# scr_precharge.net
KiCad netlist of a schematic drawn in EAGLE
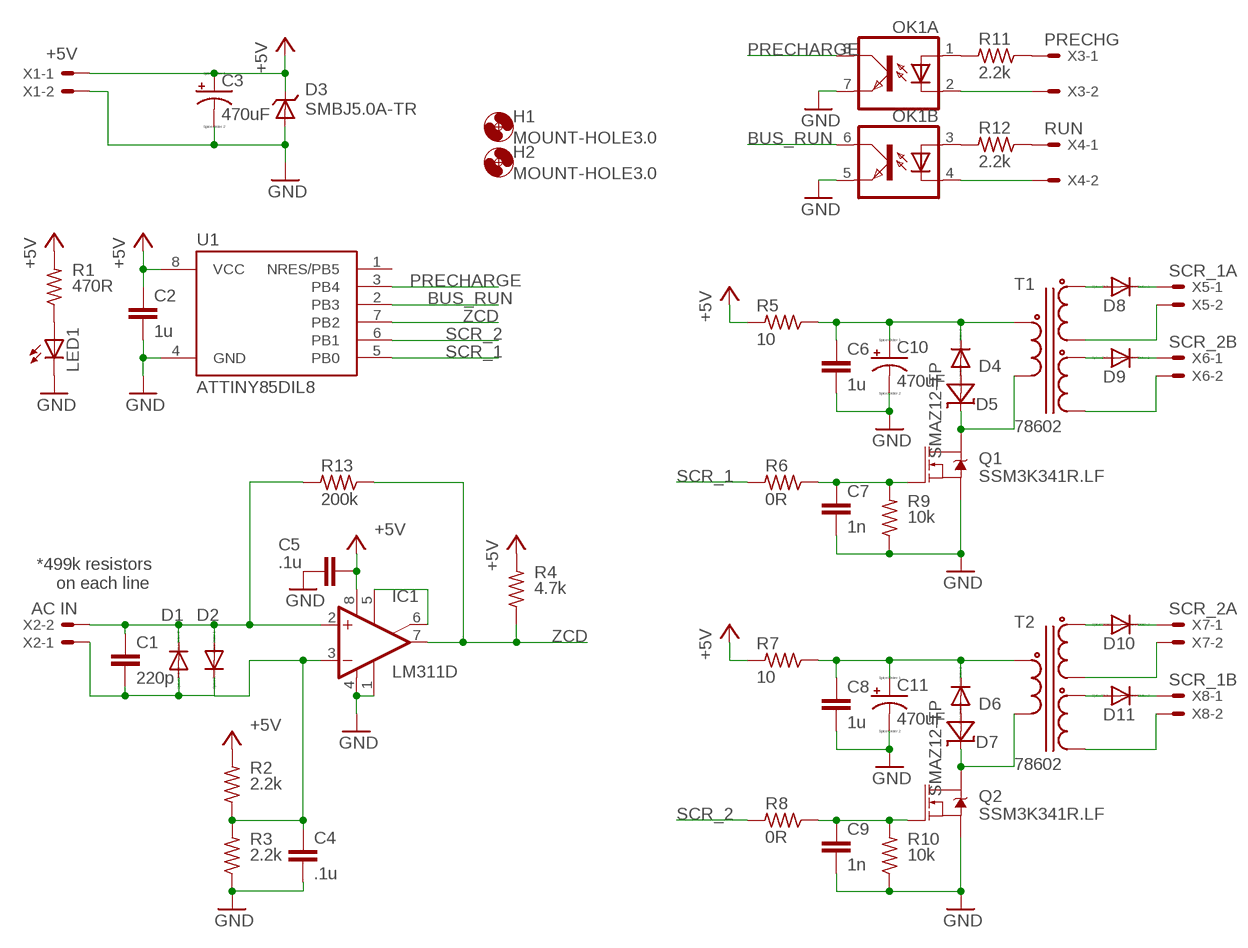
[diagram p0: schematic, sheet 1]

(export (version "E")
  (design (tool "Eeschema 10.0.6"))
  (components
    (comp (ref "C1")
      (value "220p")
      (footprint "eagle-import:C0805")
      (libsource (lib "eagle-import") (part "C-EUC0805"))
    )
    (comp (ref "C2")
      (value "1u")
      (footprint "eagle-import:C0805")
      (libsource (lib "eagle-import") (part "C-EUC0805"))
    )
    (comp (ref "C3")
      (value "470uF")
      (footprint "eagle-import:E3,5-8")
      (libsource (lib "eagle-import") (part "CPOL-USE3.5-8"))
    )
    (comp (ref "C4")
      (value ".1u")
      (footprint "eagle-import:C0805")
      (libsource (lib "eagle-import") (part "C-EUC0805"))
    )
    (comp (ref "C5")
      (value ".1u")
      (footprint "eagle-import:C0805")
      (libsource (lib "eagle-import") (part "C-EUC0805"))
    )
    (comp (ref "C6")
      (value "1u")
      (footprint "eagle-import:C0805")
      (libsource (lib "eagle-import") (part "C-EUC0805"))
    )
    (comp (ref "C7")
      (value "1n")
      (footprint "eagle-import:C0805")
      (libsource (lib "eagle-import") (part "C-EUC0805"))
    )
    (comp (ref "C8")
      (value "1u")
      (footprint "eagle-import:C0805")
      (libsource (lib "eagle-import") (part "C-EUC0805"))
    )
    (comp (ref "C9")
      (value "1n")
      (footprint "eagle-import:C0805")
      (libsource (lib "eagle-import") (part "C-EUC0805"))
    )
    (comp (ref "C10")
      (value "470uF")
      (footprint "eagle-import:E3,5-8")
      (libsource (lib "eagle-import") (part "CPOL-USE3.5-8"))
    )
    (comp (ref "C11")
      (value "470uF")
      (footprint "eagle-import:E3,5-8")
      (libsource (lib "eagle-import") (part "CPOL-USE3.5-8"))
    )
    (comp (ref "D1")
      (value "1N4148MICROMELF")
      (footprint "eagle-import:MICROMELF-W")
      (libsource (lib "eagle-import") (part "1N4148MICROMELF"))
    )
    (comp (ref "D2")
      (value "1N4148MICROMELF")
      (footprint "eagle-import:MICROMELF-W")
      (libsource (lib "eagle-import") (part "1N4148MICROMELF"))
    )
    (comp (ref "D3")
      (value "SMBJ5.0A-TR")
      (footprint "eagle-import:DO214AA")
      (libsource (lib "eagle-import") (part "SMBJ5.0A-TR"))
    )
    (comp (ref "D4")
      (value "1N4148MICROMELF")
      (footprint "eagle-import:MICROMELF-W")
      (libsource (lib "eagle-import") (part "1N4148MICROMELF"))
    )
    (comp (ref "D5")
      (value "SMAZ12-TP")
      (footprint "eagle-import:DO-214AC")
      (libsource (lib "eagle-import") (part "SMAZ12-TP"))
    )
    (comp (ref "D6")
      (value "1N4148MICROMELF")
      (footprint "eagle-import:MICROMELF-W")
      (libsource (lib "eagle-import") (part "1N4148MICROMELF"))
    )
    (comp (ref "D7")
      (value "SMAZ12-TP")
      (footprint "eagle-import:DO-214AC")
      (libsource (lib "eagle-import") (part "SMAZ12-TP"))
    )
    (comp (ref "D8")
      (value "1N4148MICROMELF")
      (footprint "eagle-import:MICROMELF-W")
      (libsource (lib "eagle-import") (part "1N4148MICROMELF"))
    )
    (comp (ref "D9")
      (value "1N4148MICROMELF")
      (footprint "eagle-import:MICROMELF-W")
      (libsource (lib "eagle-import") (part "1N4148MICROMELF"))
    )
    (comp (ref "D10")
      (value "1N4148MICROMELF")
      (footprint "eagle-import:MICROMELF-W")
      (libsource (lib "eagle-import") (part "1N4148MICROMELF"))
    )
    (comp (ref "D11")
      (value "1N4148MICROMELF")
      (footprint "eagle-import:MICROMELF-W")
      (libsource (lib "eagle-import") (part "1N4148MICROMELF"))
    )
    (comp (ref "H1")
      (value "MOUNT-HOLE3.0")
      (footprint "eagle-import:3,0")
      (libsource (lib "eagle-import") (part "MOUNT-HOLE3.0"))
    )
    (comp (ref "H2")
      (value "MOUNT-HOLE3.0")
      (footprint "eagle-import:3,0")
      (libsource (lib "eagle-import") (part "MOUNT-HOLE3.0"))
    )
    (comp (ref "IC1")
      (value "LM311D")
      (footprint "eagle-import:SO08")
      (libsource (lib "eagle-import") (part "LM311D"))
    )
    (comp (ref "LED1")
      (value "LEDCHIP-LED0805")
      (footprint "eagle-import:CHIP-LED0805")
      (libsource (lib "eagle-import") (part "LEDCHIP-LED0805"))
    )
    (comp (ref "OK1")
      (value "ILD621")
      (footprint "eagle-import:DIL08")
      (fields (field (name "MF") "VISHAY/TELEFUNKEN"))
      (libsource (lib "eagle-import") (part "ILD621"))
    )
    (comp (ref "Q1")
      (value "SSM3K341R.LF")
      (footprint "eagle-import:SOT23-3")
      (libsource (lib "eagle-import") (part "MOSFET-NCH-AO3404A"))
    )
    (comp (ref "Q2")
      (value "SSM3K341R.LF")
      (footprint "eagle-import:SOT23-3")
      (libsource (lib "eagle-import") (part "MOSFET-NCH-AO3404A"))
    )
    (comp (ref "R1")
      (value "470R")
      (footprint "eagle-import:R0805")
      (libsource (lib "eagle-import") (part "R-US_R0805"))
    )
    (comp (ref "R2")
      (value "2.2k")
      (footprint "eagle-import:R0805")
      (libsource (lib "eagle-import") (part "R-US_R0805"))
    )
    (comp (ref "R3")
      (value "2.2k")
      (footprint "eagle-import:R0805")
      (libsource (lib "eagle-import") (part "R-US_R0805"))
    )
    (comp (ref "R4")
      (value "4.7k")
      (footprint "eagle-import:R0805")
      (libsource (lib "eagle-import") (part "R-US_R0805"))
    )
    (comp (ref "R5")
      (value "10")
      (footprint "eagle-import:R2010")
      (libsource (lib "eagle-import") (part "R-US_R2010"))
    )
    (comp (ref "R6")
      (value "0R")
      (footprint "eagle-import:R0805")
      (libsource (lib "eagle-import") (part "R-US_R0805"))
    )
    (comp (ref "R7")
      (value "10")
      (footprint "eagle-import:R2010")
      (libsource (lib "eagle-import") (part "R-US_R2010"))
    )
    (comp (ref "R8")
      (value "0R")
      (footprint "eagle-import:R0805")
      (libsource (lib "eagle-import") (part "R-US_R0805"))
    )
    (comp (ref "R9")
      (value "10k")
      (footprint "eagle-import:R0805")
      (libsource (lib "eagle-import") (part "R-US_R0805"))
    )
    (comp (ref "R10")
      (value "10k")
      (footprint "eagle-import:R0805")
      (libsource (lib "eagle-import") (part "R-US_R0805"))
    )
    (comp (ref "R11")
      (value "2.2k")
      (footprint "eagle-import:R0805")
      (libsource (lib "eagle-import") (part "R-US_R0805"))
    )
    (comp (ref "R12")
      (value "2.2k")
      (footprint "eagle-import:R0805")
      (libsource (lib "eagle-import") (part "R-US_R0805"))
    )
    (comp (ref "R13")
      (value "200k")
      (footprint "eagle-import:R0805")
      (libsource (lib "eagle-import") (part "R-US_R0805"))
    )
    (comp (ref "T1")
      (value "78602")
      (footprint "eagle-import:J-STD-020D")
      (libsource (lib "eagle-import") (part "78602"))
    )
    (comp (ref "T2")
      (value "78602")
      (footprint "eagle-import:J-STD-020D")
      (libsource (lib "eagle-import") (part "78602"))
    )
    (comp (ref "U1")
      (value "ATTINY85DIL8")
      (footprint "eagle-import:DIL8")
      (libsource (lib "eagle-import") (part "ATTINY85DIL8"))
    )
    (comp (ref "X1")
      (value "+5V")
      (footprint "eagle-import:22-23-2021")
      (fields (field (name "MF") "MOLEX") (field (name "MPN") "22-23-2021"))
      (libsource (lib "eagle-import") (part "22-23-2021"))
    )
    (comp (ref "X2")
      (value "AC IN")
      (footprint "eagle-import:22-23-2021")
      (fields (field (name "MF") "MOLEX") (field (name "MPN") "22-23-2021"))
      (libsource (lib "eagle-import") (part "22-23-2021"))
    )
    (comp (ref "X3")
      (value "PRECHG")
      (footprint "eagle-import:22-23-2021")
      (fields (field (name "MF") "MOLEX") (field (name "MPN") "22-23-2021"))
      (libsource (lib "eagle-import") (part "22-23-2021"))
    )
    (comp (ref "X4")
      (value "RUN")
      (footprint "eagle-import:22-23-2021")
      (fields (field (name "MF") "MOLEX") (field (name "MPN") "22-23-2021"))
      (libsource (lib "eagle-import") (part "22-23-2021"))
    )
    (comp (ref "X5")
      (value "SCR_1A")
      (footprint "eagle-import:22-23-2021")
      (fields (field (name "MF") "MOLEX") (field (name "MPN") "22-23-2021"))
      (libsource (lib "eagle-import") (part "22-23-2021"))
    )
    (comp (ref "X6")
      (value "SCR_2B")
      (footprint "eagle-import:22-23-2021")
      (fields (field (name "MF") "MOLEX") (field (name "MPN") "22-23-2021"))
      (libsource (lib "eagle-import") (part "22-23-2021"))
    )
    (comp (ref "X7")
      (value "SCR_2A")
      (footprint "eagle-import:22-23-2021")
      (fields (field (name "MF") "MOLEX") (field (name "MPN") "22-23-2021"))
      (libsource (lib "eagle-import") (part "22-23-2021"))
    )
    (comp (ref "X8")
      (value "SCR_1B")
      (footprint "eagle-import:22-23-2021")
      (fields (field (name "MF") "MOLEX") (field (name "MPN") "22-23-2021"))
      (libsource (lib "eagle-import") (part "22-23-2021"))
    )
  )
  (nets
    (net (code "1") (name "+5V") (class "Default")
      (node (ref "C2") (pin "1") (pinfunction "1_1") (pintype "passive"))
      (node (ref "C3") (pin "+") (pinfunction "+_+") (pintype "passive"))
      (node (ref "C5") (pin "2") (pinfunction "2_2") (pintype "passive"))
      (node (ref "D3") (pin "C") (pinfunction "C_C") (pintype "passive"))
      (node (ref "IC1") (pin "8") (pinfunction "V+_8") (pintype "power_in"))
      (node (ref "R1") (pin "2") (pinfunction "2_2") (pintype "passive"))
      (node (ref "R2") (pin "2") (pinfunction "2_2") (pintype "passive"))
      (node (ref "R4") (pin "2") (pinfunction "2_2") (pintype "passive"))
      (node (ref "R5") (pin "2") (pinfunction "2_2") (pintype "passive"))
      (node (ref "R7") (pin "2") (pinfunction "2_2") (pintype "passive"))
      (node (ref "U1") (pin "8") (pinfunction "VCC_8") (pintype "power_in"))
      (node (ref "X1") (pin "1") (pinfunction "S_1") (pintype "passive"))
    )
    (net (code "2") (name "/BUS_RUN") (class "Default")
      (node (ref "OK1") (pin "6") (pinfunction "COL_6") (pintype "passive"))
      (node (ref "U1") (pin "2") (pinfunction "PB3_2") (pintype "bidirectional"))
    )
    (net (code "3") (name "/PRECHARGE") (class "Default")
      (node (ref "OK1") (pin "8") (pinfunction "COL_8") (pintype "passive"))
      (node (ref "U1") (pin "3") (pinfunction "PB4_3") (pintype "bidirectional"))
    )
    (net (code "4") (name "/SCR_1") (class "Default")
      (node (ref "R6") (pin "2") (pinfunction "2_2") (pintype "passive"))
      (node (ref "U1") (pin "5") (pinfunction "PB0_5") (pintype "bidirectional"))
    )
    (net (code "5") (name "/SCR_2") (class "Default")
      (node (ref "R8") (pin "2") (pinfunction "2_2") (pintype "passive"))
      (node (ref "U1") (pin "6") (pinfunction "PB1_6") (pintype "bidirectional"))
    )
    (net (code "6") (name "/ZCD") (class "Default")
      (node (ref "IC1") (pin "7") (pinfunction "OUT_7") (pintype "output"))
      (node (ref "R13") (pin "1") (pinfunction "1_1") (pintype "passive"))
      (node (ref "R4") (pin "1") (pinfunction "1_1") (pintype "passive"))
      (node (ref "U1") (pin "7") (pinfunction "PB2_7") (pintype "bidirectional"))
    )
    (net (code "7") (name "GND") (class "Default")
      (node (ref "C10") (pin "-") (pinfunction "-_-") (pintype "passive"))
      (node (ref "C11") (pin "-") (pinfunction "-_-") (pintype "passive"))
      (node (ref "C2") (pin "2") (pinfunction "2_2") (pintype "passive"))
      (node (ref "C3") (pin "-") (pinfunction "-_-") (pintype "passive"))
      (node (ref "C4") (pin "2") (pinfunction "2_2") (pintype "passive"))
      (node (ref "C5") (pin "1") (pinfunction "1_1") (pintype "passive"))
      (node (ref "C6") (pin "2") (pinfunction "2_2") (pintype "passive"))
      (node (ref "C7") (pin "2") (pinfunction "2_2") (pintype "passive"))
      (node (ref "C8") (pin "2") (pinfunction "2_2") (pintype "passive"))
      (node (ref "C9") (pin "2") (pinfunction "2_2") (pintype "passive"))
      (node (ref "D3") (pin "A") (pinfunction "A_A") (pintype "passive"))
      (node (ref "IC1") (pin "1") (pinfunction "GND_1") (pintype "passive"))
      (node (ref "IC1") (pin "4") (pinfunction "V-_4") (pintype "power_in"))
      (node (ref "LED1") (pin "C") (pinfunction "C_C") (pintype "passive"))
      (node (ref "OK1") (pin "5") (pinfunction "EMIT_5") (pintype "passive"))
      (node (ref "OK1") (pin "7") (pinfunction "EMIT_7") (pintype "passive"))
      (node (ref "Q1") (pin "2") (pinfunction "S_2") (pintype "bidirectional"))
      (node (ref "Q2") (pin "2") (pinfunction "S_2") (pintype "bidirectional"))
      (node (ref "R10") (pin "1") (pinfunction "1_1") (pintype "passive"))
      (node (ref "R3") (pin "1") (pinfunction "1_1") (pintype "passive"))
      (node (ref "R9") (pin "1") (pinfunction "1_1") (pintype "passive"))
      (node (ref "U1") (pin "4") (pinfunction "GND_4") (pintype "power_in"))
      (node (ref "X1") (pin "2") (pinfunction "S_2") (pintype "passive"))
    )
    (net (code "8") (name "Net-(C10-Pad+)") (class "Default")
      (node (ref "C10") (pin "+") (pinfunction "+_+") (pintype "passive"))
      (node (ref "C6") (pin "1") (pinfunction "1_1") (pintype "passive"))
      (node (ref "D4") (pin "C") (pinfunction "C_C") (pintype "passive"))
      (node (ref "R5") (pin "1") (pinfunction "1_1") (pintype "passive"))
      (node (ref "T1") (pin "P$1") (pinfunction "P$1_P$1") (pintype "bidirectional"))
    )
    (net (code "9") (name "Net-(C11-Pad+)") (class "Default")
      (node (ref "C11") (pin "+") (pinfunction "+_+") (pintype "passive"))
      (node (ref "C8") (pin "1") (pinfunction "1_1") (pintype "passive"))
      (node (ref "D6") (pin "C") (pinfunction "C_C") (pintype "passive"))
      (node (ref "R7") (pin "1") (pinfunction "1_1") (pintype "passive"))
      (node (ref "T2") (pin "P$1") (pinfunction "P$1_P$1") (pintype "bidirectional"))
    )
    (net (code "10") (name "Net-(D4-PadA)") (class "Default")
      (node (ref "D4") (pin "A") (pinfunction "A_A") (pintype "passive"))
      (node (ref "D5") (pin "A") (pinfunction "A_A") (pintype "passive"))
    )
    (net (code "11") (name "Net-(D6-PadA)") (class "Default")
      (node (ref "D6") (pin "A") (pinfunction "A_A") (pintype "passive"))
      (node (ref "D7") (pin "A") (pinfunction "A_A") (pintype "passive"))
    )
    (net (code "12") (name "Net-(D8-PadA)") (class "Default")
      (node (ref "D8") (pin "A") (pinfunction "A_A") (pintype "passive"))
      (node (ref "T1") (pin "P$2") (pinfunction "P$2_P$2") (pintype "bidirectional"))
    )
    (net (code "13") (name "Net-(D9-PadA)") (class "Default")
      (node (ref "D9") (pin "A") (pinfunction "A_A") (pintype "passive"))
      (node (ref "T1") (pin "P$3") (pinfunction "P$3_P$3") (pintype "bidirectional"))
    )
    (net (code "14") (name "Net-(D10-PadA)") (class "Default")
      (node (ref "D10") (pin "A") (pinfunction "A_A") (pintype "passive"))
      (node (ref "T2") (pin "P$2") (pinfunction "P$2_P$2") (pintype "bidirectional"))
    )
    (net (code "15") (name "Net-(D11-PadA)") (class "Default")
      (node (ref "D11") (pin "A") (pinfunction "A_A") (pintype "passive"))
      (node (ref "T2") (pin "P$3") (pinfunction "P$3_P$3") (pintype "bidirectional"))
    )
    (net (code "16") (name "Net-(IC1-+IN)") (class "Default")
      (node (ref "C1") (pin "1") (pinfunction "1_1") (pintype "passive"))
      (node (ref "D1") (pin "C") (pinfunction "C_C") (pintype "passive"))
      (node (ref "D2") (pin "A") (pinfunction "A_A") (pintype "passive"))
      (node (ref "IC1") (pin "2") (pinfunction "+IN_2") (pintype "input"))
      (node (ref "R13") (pin "2") (pinfunction "2_2") (pintype "passive"))
      (node (ref "X2") (pin "2") (pinfunction "S_2") (pintype "passive"))
    )
    (net (code "17") (name "Net-(IC1--IN)") (class "Default")
      (node (ref "C1") (pin "2") (pinfunction "2_2") (pintype "passive"))
      (node (ref "C4") (pin "1") (pinfunction "1_1") (pintype "passive"))
      (node (ref "D1") (pin "A") (pinfunction "A_A") (pintype "passive"))
      (node (ref "D2") (pin "C") (pinfunction "C_C") (pintype "passive"))
      (node (ref "IC1") (pin "3") (pinfunction "-IN_3") (pintype "input"))
      (node (ref "R2") (pin "1") (pinfunction "1_1") (pintype "passive"))
      (node (ref "R3") (pin "2") (pinfunction "2_2") (pintype "passive"))
      (node (ref "X2") (pin "1") (pinfunction "S_1") (pintype "passive"))
    )
    (net (code "18") (name "Net-(IC1-ON)") (class "Default")
      (node (ref "IC1") (pin "5") (pinfunction "ON_5") (pintype "passive"))
      (node (ref "IC1") (pin "6") (pinfunction "ON/STR_6") (pintype "passive"))
    )
    (net (code "19") (name "Net-(LED1-PadA)") (class "Default")
      (node (ref "LED1") (pin "A") (pinfunction "A_A") (pintype "passive"))
      (node (ref "R1") (pin "1") (pinfunction "1_1") (pintype "passive"))
    )
    (net (code "20") (name "Net-(OK1A-A)") (class "Default")
      (node (ref "OK1") (pin "1") (pinfunction "A_1") (pintype "passive"))
      (node (ref "R11") (pin "2") (pinfunction "2_2") (pintype "passive"))
    )
    (net (code "21") (name "Net-(OK1A-C)") (class "Default")
      (node (ref "OK1") (pin "2") (pinfunction "C_2") (pintype "passive"))
      (node (ref "X3") (pin "2") (pinfunction "S_2") (pintype "passive"))
    )
    (net (code "22") (name "Net-(OK1B-A)") (class "Default")
      (node (ref "OK1") (pin "3") (pinfunction "A_3") (pintype "passive"))
      (node (ref "R12") (pin "2") (pinfunction "2_2") (pintype "passive"))
    )
    (net (code "23") (name "Net-(OK1B-C)") (class "Default")
      (node (ref "OK1") (pin "4") (pinfunction "C_4") (pintype "passive"))
      (node (ref "X4") (pin "2") (pinfunction "S_2") (pintype "passive"))
    )
    (net (code "24") (name "Net-(Q1-D)") (class "Default")
      (node (ref "D5") (pin "C") (pinfunction "C_C") (pintype "passive"))
      (node (ref "Q1") (pin "3") (pinfunction "D_3") (pintype "bidirectional"))
      (node (ref "T1") (pin "P$6") (pinfunction "P$6_P$6") (pintype "bidirectional"))
    )
    (net (code "25") (name "Net-(Q1-G)") (class "Default")
      (node (ref "C7") (pin "1") (pinfunction "1_1") (pintype "passive"))
      (node (ref "Q1") (pin "1") (pinfunction "G_1") (pintype "bidirectional"))
      (node (ref "R6") (pin "1") (pinfunction "1_1") (pintype "passive"))
      (node (ref "R9") (pin "2") (pinfunction "2_2") (pintype "passive"))
    )
    (net (code "26") (name "Net-(Q2-D)") (class "Default")
      (node (ref "D7") (pin "C") (pinfunction "C_C") (pintype "passive"))
      (node (ref "Q2") (pin "3") (pinfunction "D_3") (pintype "bidirectional"))
      (node (ref "T2") (pin "P$6") (pinfunction "P$6_P$6") (pintype "bidirectional"))
    )
    (net (code "27") (name "Net-(Q2-G)") (class "Default")
      (node (ref "C9") (pin "1") (pinfunction "1_1") (pintype "passive"))
      (node (ref "Q2") (pin "1") (pinfunction "G_1") (pintype "bidirectional"))
      (node (ref "R10") (pin "2") (pinfunction "2_2") (pintype "passive"))
      (node (ref "R8") (pin "1") (pinfunction "1_1") (pintype "passive"))
    )
    (net (code "28") (name "Net-(X3A-S)") (class "Default")
      (node (ref "R11") (pin "1") (pinfunction "1_1") (pintype "passive"))
      (node (ref "X3") (pin "1") (pinfunction "S_1") (pintype "passive"))
    )
    (net (code "29") (name "Net-(X4A-S)") (class "Default")
      (node (ref "R12") (pin "1") (pinfunction "1_1") (pintype "passive"))
      (node (ref "X4") (pin "1") (pinfunction "S_1") (pintype "passive"))
    )
    (net (code "30") (name "Net-(X5A-S)") (class "Default")
      (node (ref "D8") (pin "C") (pinfunction "C_C") (pintype "passive"))
      (node (ref "X5") (pin "1") (pinfunction "S_1") (pintype "passive"))
    )
    (net (code "31") (name "Net-(X5B-S)") (class "Default")
      (node (ref "T1") (pin "P$5") (pinfunction "P$5_P$5") (pintype "bidirectional"))
      (node (ref "X5") (pin "2") (pinfunction "S_2") (pintype "passive"))
    )
    (net (code "32") (name "Net-(X6A-S)") (class "Default")
      (node (ref "D9") (pin "C") (pinfunction "C_C") (pintype "passive"))
      (node (ref "X6") (pin "1") (pinfunction "S_1") (pintype "passive"))
    )
    (net (code "33") (name "Net-(X6B-S)") (class "Default")
      (node (ref "T1") (pin "P$4") (pinfunction "P$4_P$4") (pintype "bidirectional"))
      (node (ref "X6") (pin "2") (pinfunction "S_2") (pintype "passive"))
    )
    (net (code "34") (name "Net-(X7A-S)") (class "Default")
      (node (ref "D10") (pin "C") (pinfunction "C_C") (pintype "passive"))
      (node (ref "X7") (pin "1") (pinfunction "S_1") (pintype "passive"))
    )
    (net (code "35") (name "Net-(X7B-S)") (class "Default")
      (node (ref "T2") (pin "P$5") (pinfunction "P$5_P$5") (pintype "bidirectional"))
      (node (ref "X7") (pin "2") (pinfunction "S_2") (pintype "passive"))
    )
    (net (code "36") (name "Net-(X8A-S)") (class "Default")
      (node (ref "D11") (pin "C") (pinfunction "C_C") (pintype "passive"))
      (node (ref "X8") (pin "1") (pinfunction "S_1") (pintype "passive"))
    )
    (net (code "37") (name "Net-(X8B-S)") (class "Default")
      (node (ref "T2") (pin "P$4") (pinfunction "P$4_P$4") (pintype "bidirectional"))
      (node (ref "X8") (pin "2") (pinfunction "S_2") (pintype "passive"))
    )
    (net (code "38") (name "unconnected-(U1-NRES{slash}PB5-Pad1)") (class "Default")
      (node (ref "U1") (pin "1") (pinfunction "NRES/PB5_1") (pintype "bidirectional"))
    )
  )
)
